# MODULE_FPGA.net
KiCad netlist of a schematic drawn in Altium Designer
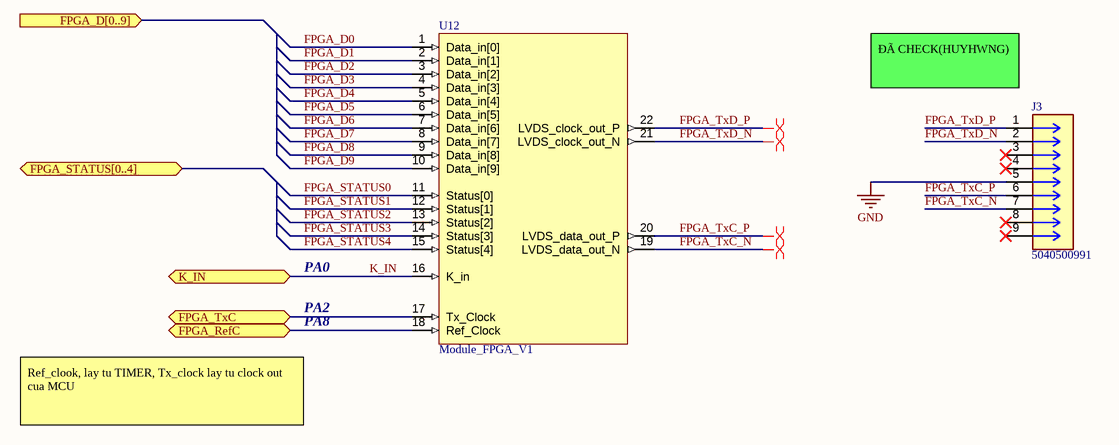
[diagram p0: MODULE_FPGA.SchDoc]

(export (version "E")
  (design (tool "Eeschema 10.0.6"))
  (components
    (comp (ref "J3")
      (value "5040500991")
      (footprint "5040500991")
      (description "Connector Header Surface Mount, Right Angle 9 position 0.059\" (1.50mm)")
      (libsource (lib "COMM_SCHLIB") (part "5040500991"))
    )
    (comp (ref "U12")
      (value "Module_FPGA_V1")
      (footprint "MODULE_FPGA")
      (libsource (lib "3_HuyHung") (part "Module_FPGA_V1"))
    )
  )
  (nets
    (net (code "1") (name "/FPGA_D0") (class "Default")
      (node (ref "U12") (pin "1") (pinfunction "Data_in[0]_1") (pintype "input"))
    )
    (net (code "2") (name "/FPGA_D1") (class "Default")
      (node (ref "U12") (pin "2") (pinfunction "Data_in[1]_2") (pintype "input"))
    )
    (net (code "3") (name "/FPGA_D2") (class "Default")
      (node (ref "U12") (pin "3") (pinfunction "Data_in[2]_3") (pintype "input"))
    )
    (net (code "4") (name "/FPGA_D3") (class "Default")
      (node (ref "U12") (pin "4") (pinfunction "Data_in[3]_4") (pintype "input"))
    )
    (net (code "5") (name "/FPGA_D4") (class "Default")
      (node (ref "U12") (pin "5") (pinfunction "Data_in[4]_5") (pintype "input"))
    )
    (net (code "6") (name "/FPGA_D5") (class "Default")
      (node (ref "U12") (pin "6") (pinfunction "Data_in[5]_6") (pintype "input"))
    )
    (net (code "7") (name "/FPGA_D6") (class "Default")
      (node (ref "U12") (pin "7") (pinfunction "Data_in[6]_7") (pintype "input"))
    )
    (net (code "8") (name "/FPGA_D7") (class "Default")
      (node (ref "U12") (pin "8") (pinfunction "Data_in[7]_8") (pintype "input"))
    )
    (net (code "9") (name "/FPGA_D8") (class "Default")
      (node (ref "U12") (pin "9") (pinfunction "Data_in[8]_9") (pintype "input"))
    )
    (net (code "10") (name "/FPGA_D9") (class "Default")
      (node (ref "U12") (pin "10") (pinfunction "Data_in[9]_10") (pintype "input"))
    )
    (net (code "12") (name "/FPGA_RefC") (class "Default")
      (node (ref "U12") (pin "18") (pinfunction "Ref_Clock_18") (pintype "input"))
    )
    (net (code "13") (name "/FPGA_STATUS0") (class "Default")
      (node (ref "U12") (pin "11") (pinfunction "Status[0]_11") (pintype "input"))
    )
    (net (code "14") (name "/FPGA_STATUS1") (class "Default")
      (node (ref "U12") (pin "12") (pinfunction "Status[1]_12") (pintype "input"))
    )
    (net (code "15") (name "/FPGA_STATUS2") (class "Default")
      (node (ref "U12") (pin "13") (pinfunction "Status[2]_13") (pintype "input"))
    )
    (net (code "16") (name "/FPGA_STATUS3") (class "Default")
      (node (ref "U12") (pin "14") (pinfunction "Status[3]_14") (pintype "input"))
    )
    (net (code "17") (name "/FPGA_STATUS4") (class "Default")
      (node (ref "U12") (pin "15") (pinfunction "Status[4]_15") (pintype "input"))
    )
    (net (code "19") (name "/FPGA_TxC") (class "Default")
      (node (ref "U12") (pin "17") (pinfunction "Tx_Clock_17") (pintype "input"))
    )
    (net (code "20") (name "/FPGA_TxC_N") (class "Default")
      (node (ref "J3") (pin "7") (pinfunction "7_7") (pintype "passive"))
      (node (ref "U12") (pin "19") (pinfunction "LVDS_data_out_N_19") (pintype "output"))
    )
    (net (code "21") (name "/FPGA_TxC_P") (class "Default")
      (node (ref "J3") (pin "6") (pinfunction "6_6") (pintype "passive"))
      (node (ref "U12") (pin "20") (pinfunction "LVDS_data_out_P_20") (pintype "output"))
    )
    (net (code "22") (name "/FPGA_TxD_N") (class "Default")
      (node (ref "J3") (pin "2") (pinfunction "2_2") (pintype "passive"))
      (node (ref "U12") (pin "21") (pinfunction "LVDS_clock_out_N_21") (pintype "output"))
    )
    (net (code "23") (name "/FPGA_TxD_P") (class "Default")
      (node (ref "J3") (pin "1") (pinfunction "1_1") (pintype "passive"))
      (node (ref "U12") (pin "22") (pinfunction "LVDS_clock_out_P_22") (pintype "output"))
    )
    (net (code "24") (name "/K_IN") (class "Default")
      (node (ref "U12") (pin "16") (pinfunction "K_in_16") (pintype "input"))
    )
    (net (code "25") (name "GND") (class "Default")
      (node (ref "J3") (pin "5") (pinfunction "5_5") (pintype "passive"))
    )
    (net (code "26") (name "unconnected-(J3-Pad3)") (class "Default")
      (node (ref "J3") (pin "3") (pinfunction "3_3") (pintype "passive+no_connect"))
    )
    (net (code "27") (name "unconnected-(J3-Pad4)") (class "Default")
      (node (ref "J3") (pin "4") (pinfunction "4_4") (pintype "passive+no_connect"))
    )
    (net (code "28") (name "unconnected-(J3-Pad8)") (class "Default")
      (node (ref "J3") (pin "8") (pinfunction "8_8") (pintype "passive+no_connect"))
    )
    (net (code "29") (name "unconnected-(J3-Pad9)") (class "Default")
      (node (ref "J3") (pin "9") (pinfunction "9_9") (pintype "passive+no_connect"))
    )
  )
)
